# Sch_DSS2_NolanJennifer.net
KiCad netlist of a schematic drawn in Altium Designer
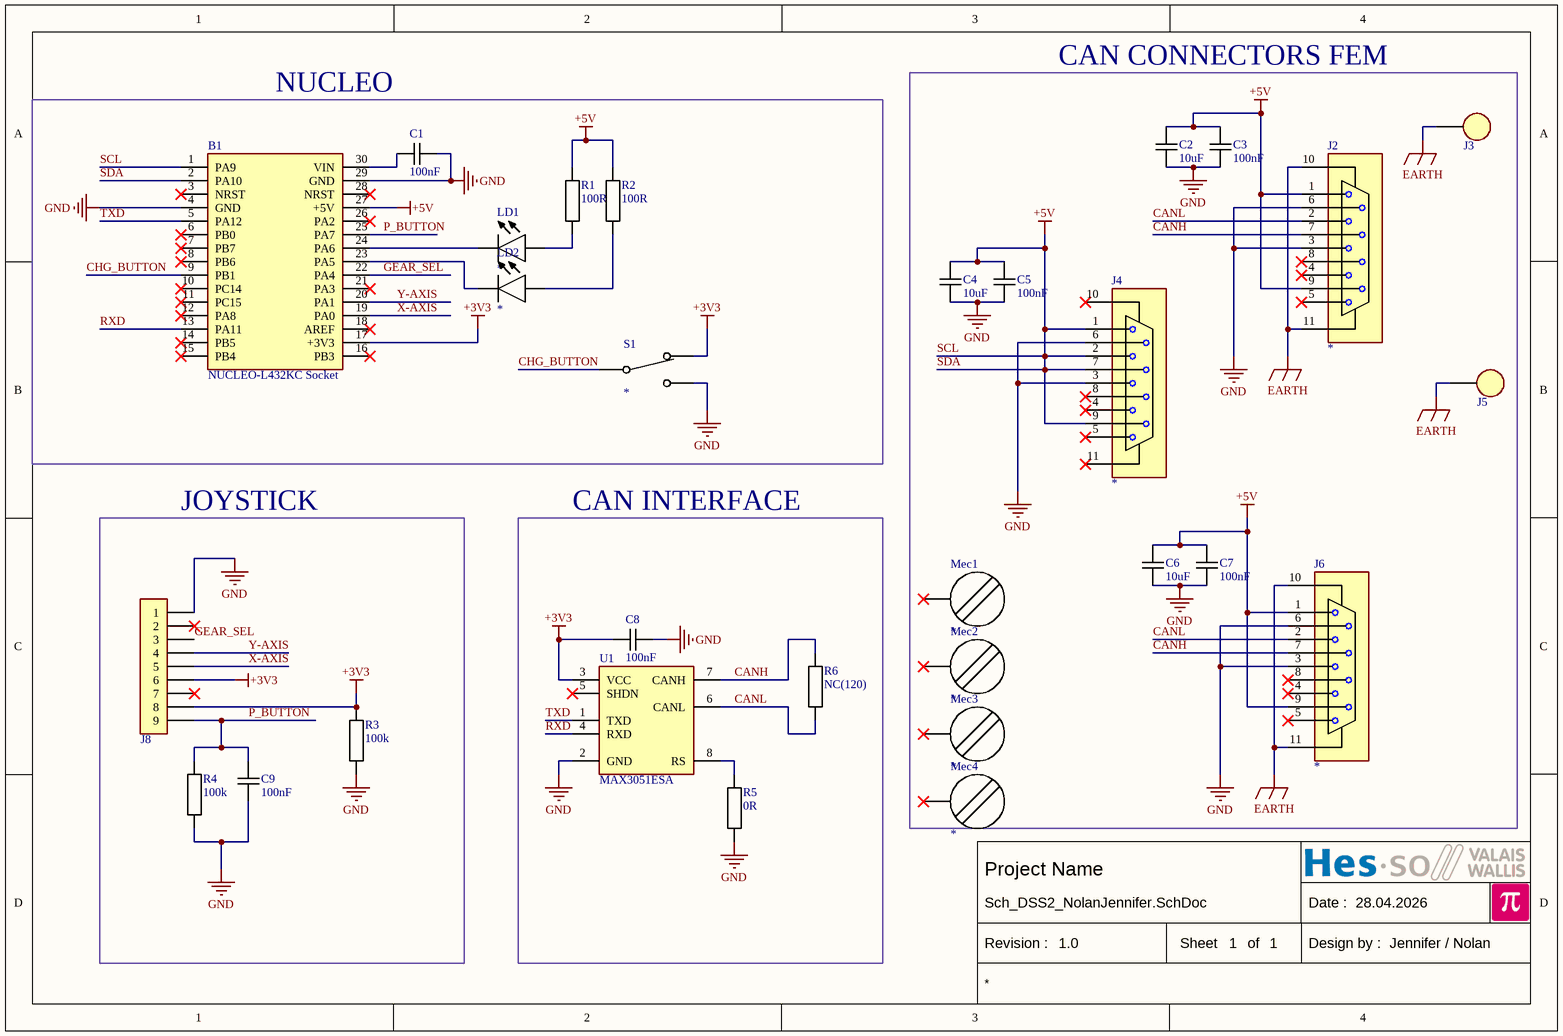
[diagram p0: Sch_DSS2_NolanJennifer.SchDoc]

(export (version "E")
  (design (tool "Eeschema 10.0.6"))
  (components
    (comp (ref "B1")
      (value "NUCLEO-L432KC Socket")
      (footprint "NUCLEO-L432KC Socket")
      (description "ARM Cortex based board")
      (libsource (lib "DevBoard") (part "NUCLEO-L432KC Socket"))
    )
    (comp (ref "C1")
      (value "100nF")
      (footprint "CAPACITOR 2012 REFLOW")
      (description "Capacitor")
      (libsource (lib "Capacitor") (part "Capacitor"))
    )
    (comp (ref "C2")
      (value "10uF")
      (footprint "CAPACITOR 2012 REFLOW")
      (description "Capacitor")
      (libsource (lib "Capacitor") (part "Capacitor"))
    )
    (comp (ref "C3")
      (value "100nF")
      (footprint "CAPACITOR 2012 REFLOW")
      (description "Capacitor")
      (libsource (lib "Capacitor") (part "Capacitor"))
    )
    (comp (ref "C4")
      (value "10uF")
      (footprint "CAPACITOR 2012 REFLOW")
      (description "Capacitor")
      (libsource (lib "Capacitor") (part "Capacitor"))
    )
    (comp (ref "C5")
      (value "100nF")
      (footprint "CAPACITOR 2012 REFLOW")
      (description "Capacitor")
      (libsource (lib "Capacitor") (part "Capacitor"))
    )
    (comp (ref "C6")
      (value "10uF")
      (footprint "CAPACITOR 2012 REFLOW")
      (description "Capacitor")
      (libsource (lib "Capacitor") (part "Capacitor"))
    )
    (comp (ref "C7")
      (value "100nF")
      (footprint "CAPACITOR 2012 REFLOW")
      (description "Capacitor")
      (libsource (lib "Capacitor") (part "Capacitor"))
    )
    (comp (ref "C8")
      (value "100nF")
      (footprint "CAPACITOR 2012 REFLOW")
      (description "Capacitor")
      (libsource (lib "Capacitor") (part "Capacitor"))
    )
    (comp (ref "C9")
      (value "100nF")
      (footprint "CAPACITOR 2012 REFLOW")
      (description "Capacitor")
      (libsource (lib "Capacitor") (part "Capacitor"))
    )
    (comp (ref "J2")
      (value "*")
      (footprint "D-SUB 9 FEM RND 205-00769")
      (description "D-Subminiature 9 way Socket Right Angle")
      (libsource (lib "Connector") (part "D-SUB 9 FEM GROUNDED"))
    )
    (comp (ref "J3")
      (value "3867B.68")
      (footprint "FASTON 6.3mm P5.0")
      (description "Faston Right angle Vogt 3867B.68")
      (libsource (lib "Connector") (part "FASTON 6.3mm P5.0"))
    )
    (comp (ref "J4")
      (value "*")
      (footprint "D-SUB 9 FEM RND 205-00769")
      (description "D-Subminiature 9 way Socket Right Angle")
      (libsource (lib "Connector") (part "D-SUB 9 FEM GROUNDED"))
    )
    (comp (ref "J5")
      (value "3867B.68")
      (footprint "FASTON 6.3mm P5.0")
      (description "Faston Right angle Vogt 3867B.68")
      (libsource (lib "Connector") (part "FASTON 6.3mm P5.0"))
    )
    (comp (ref "J6")
      (value "*")
      (footprint "D-SUB 9 FEM RND 205-00769")
      (description "D-Subminiature 9 way Socket Right Angle")
      (libsource (lib "Connector") (part "D-SUB 9 FEM GROUNDED"))
    )
    (comp (ref "J8")
      (value "*")
      (footprint "PinHeader1x9 P2.54")
      (description "Plug connector")
      (libsource (lib "PinHeader") (part "PinHeader1x9"))
    )
    (comp (ref "LD1")
      (value "*")
      (footprint "LED 3216 REFLOW")
      (description "LED generic")
      (libsource (lib "Diode") (part "LED"))
    )
    (comp (ref "LD2")
      (value "*")
      (footprint "LED 3216 REFLOW")
      (description "LED generic")
      (libsource (lib "Diode") (part "LED"))
    )
    (comp (ref "Mec1")
      (value "*")
      (footprint "Screw M3X5 Connected")
      (description "Screw Connected BN330")
      (libsource (lib "Mechanic") (part "Screw Connected"))
    )
    (comp (ref "Mec2")
      (value "*")
      (footprint "Screw M3X5 Connected")
      (description "Screw Connected BN330")
      (libsource (lib "Mechanic") (part "Screw Connected"))
    )
    (comp (ref "Mec3")
      (value "*")
      (footprint "Screw M3X5 Connected")
      (description "Screw Connected BN330")
      (libsource (lib "Mechanic") (part "Screw Connected"))
    )
    (comp (ref "Mec4")
      (value "*")
      (footprint "Screw M3X5 Connected")
      (description "Screw Connected BN330")
      (libsource (lib "Mechanic") (part "Screw Connected"))
    )
    (comp (ref "R1")
      (value "100R")
      (footprint "RESISTOR 2012 REFLOW")
      (description "Resistor")
      (libsource (lib "Resistor") (part "Resistor"))
    )
    (comp (ref "R2")
      (value "100R")
      (footprint "RESISTOR 2012 REFLOW")
      (description "Resistor")
      (libsource (lib "Resistor") (part "Resistor"))
    )
    (comp (ref "R3")
      (value "100k")
      (footprint "RESISTOR 2012 REFLOW")
      (description "Resistor")
      (libsource (lib "Resistor") (part "Resistor"))
    )
    (comp (ref "R4")
      (value "100k")
      (footprint "RESISTOR 2012 REFLOW")
      (description "Resistor")
      (libsource (lib "Resistor") (part "Resistor"))
    )
    (comp (ref "R5")
      (value "0R")
      (footprint "RESISTOR 2012 REFLOW")
      (description "Resistor")
      (libsource (lib "Resistor") (part "Resistor"))
    )
    (comp (ref "R6")
      (value "NC(120)")
      (footprint "RESISTOR 2012 REFLOW")
      (description "Resistor")
      (libsource (lib "Resistor") (part "Resistor"))
    )
    (comp (ref "S1")
      (value "*")
      (footprint "SLIDE SWITCH Knitter MFP120")
      (description "Slide Switch 1Pole ON-ON")
      (fields (field (name "ALTIUM_VALUE") "*"))
      (libsource (lib "Button") (part "Slide Switch 1Pole ON-ON"))
    )
    (comp (ref "U1")
      (value "MAX3051ESA")
      (footprint "SO8 P1.27 C4.0X5.0 H1.75")
      (description "+3.3V, 1Mbps, Low-Supply-Current CAN Transceiver")
      (libsource (lib "IntegratedCircuit") (part "MAX3051ESA"))
    )
  )
  (nets
    (net (code "1") (name "+3V3") (class "Default")
      (node (ref "B1") (pin "17") (pinfunction "+3V3_17") (pintype "passive"))
      (node (ref "C8") (pin "1") (pinfunction "1_1") (pintype "passive"))
      (node (ref "J8") (pin "6") (pinfunction "6_6") (pintype "passive"))
      (node (ref "J8") (pin "8") (pinfunction "8_8") (pintype "passive"))
      (node (ref "R3") (pin "2") (pinfunction "2_2") (pintype "passive"))
      (node (ref "S1") (pin "1") (pinfunction "NC_1") (pintype "passive"))
      (node (ref "U1") (pin "3") (pinfunction "VCC_3") (pintype "passive"))
    )
    (net (code "2") (name "+5V") (class "Default")
      (node (ref "B1") (pin "1") (pinfunction "PA9_1") (pintype "passive"))
      (node (ref "B1") (pin "2") (pinfunction "PA10_2") (pintype "passive"))
      (node (ref "B1") (pin "27") (pinfunction "+5V_27") (pintype "passive"))
      (node (ref "C2") (pin "2") (pinfunction "2_2") (pintype "passive"))
      (node (ref "C3") (pin "2") (pinfunction "2_2") (pintype "passive"))
      (node (ref "C4") (pin "2") (pinfunction "2_2") (pintype "passive"))
      (node (ref "C5") (pin "2") (pinfunction "2_2") (pintype "passive"))
      (node (ref "C6") (pin "2") (pinfunction "2_2") (pintype "passive"))
      (node (ref "C7") (pin "2") (pinfunction "2_2") (pintype "passive"))
      (node (ref "J2") (pin "1") (pintype "passive"))
      (node (ref "J2") (pin "9") (pintype "passive"))
      (node (ref "J4") (pin "1") (pintype "passive"))
      (node (ref "J4") (pin "2") (pintype "passive"))
      (node (ref "J4") (pin "7") (pintype "passive"))
      (node (ref "J4") (pin "9") (pintype "passive"))
      (node (ref "J6") (pin "1") (pintype "passive"))
      (node (ref "J6") (pin "9") (pintype "passive"))
      (node (ref "R1") (pin "2") (pinfunction "2_2") (pintype "passive"))
      (node (ref "R2") (pin "2") (pinfunction "2_2") (pintype "passive"))
    )
    (net (code "3") (name "/CANH") (class "Default")
      (node (ref "J2") (pin "7") (pintype "passive"))
      (node (ref "J6") (pin "7") (pintype "passive"))
      (node (ref "R6") (pin "2") (pinfunction "2_2") (pintype "passive"))
      (node (ref "U1") (pin "7") (pinfunction "CANH_7") (pintype "passive"))
    )
    (net (code "4") (name "/CANL") (class "Default")
      (node (ref "J2") (pin "2") (pintype "passive"))
      (node (ref "J6") (pin "2") (pintype "passive"))
      (node (ref "R6") (pin "1") (pinfunction "1_1") (pintype "passive"))
      (node (ref "U1") (pin "6") (pinfunction "CANL_6") (pintype "passive"))
    )
    (net (code "5") (name "/CHG_BUTTON") (class "Default")
      (node (ref "B1") (pin "9") (pinfunction "PB1_9") (pintype "passive"))
      (node (ref "S1") (pin "2") (pinfunction "com_2") (pintype "passive"))
    )
    (net (code "6") (name "/GEAR_SEL") (class "Default")
      (node (ref "B1") (pin "22") (pinfunction "PA4_22") (pintype "passive"))
      (node (ref "J8") (pin "3") (pinfunction "3_3") (pintype "passive"))
    )
    (net (code "7") (name "/P_BUTTON") (class "Default")
      (node (ref "B1") (pin "25") (pinfunction "PA7_25") (pintype "passive"))
      (node (ref "C9") (pin "2") (pinfunction "2_2") (pintype "passive"))
      (node (ref "J8") (pin "9") (pinfunction "9_9") (pintype "passive"))
      (node (ref "R4") (pin "2") (pinfunction "2_2") (pintype "passive"))
    )
    (net (code "8") (name "/RXD") (class "Default")
      (node (ref "B1") (pin "13") (pinfunction "PA11_13") (pintype "passive"))
      (node (ref "U1") (pin "4") (pinfunction "RXD_4") (pintype "passive"))
    )
    (net (code "9") (name "/TXD") (class "Default")
      (node (ref "B1") (pin "5") (pinfunction "PA12_5") (pintype "passive"))
      (node (ref "U1") (pin "1") (pinfunction "TXD_1") (pintype "passive"))
    )
    (net (code "10") (name "/X-AXIS") (class "Default")
      (node (ref "B1") (pin "19") (pinfunction "PA0_19") (pintype "passive"))
      (node (ref "J8") (pin "5") (pinfunction "5_5") (pintype "passive"))
    )
    (net (code "11") (name "/Y-AXIS") (class "Default")
      (node (ref "B1") (pin "20") (pinfunction "PA1_20") (pintype "passive"))
      (node (ref "J8") (pin "4") (pinfunction "4_4") (pintype "passive"))
    )
    (net (code "12") (name "EARTH") (class "Default")
      (node (ref "J2") (pin "10") (pintype "passive"))
      (node (ref "J2") (pin "11") (pintype "passive"))
      (node (ref "J3") (pin "1") (pinfunction "1_1") (pintype "passive"))
      (node (ref "J5") (pin "1") (pinfunction "1_1") (pintype "passive"))
      (node (ref "J6") (pin "10") (pintype "passive"))
      (node (ref "J6") (pin "11") (pintype "passive"))
    )
    (net (code "13") (name "GND") (class "Default")
      (node (ref "B1") (pin "29") (pinfunction "GND_29") (pintype "passive"))
      (node (ref "B1") (pin "4") (pinfunction "GND_4") (pintype "passive"))
      (node (ref "C1") (pin "2") (pinfunction "2_2") (pintype "passive"))
      (node (ref "C2") (pin "1") (pinfunction "1_1") (pintype "passive"))
      (node (ref "C3") (pin "1") (pinfunction "1_1") (pintype "passive"))
      (node (ref "C4") (pin "1") (pinfunction "1_1") (pintype "passive"))
      (node (ref "C5") (pin "1") (pinfunction "1_1") (pintype "passive"))
      (node (ref "C6") (pin "1") (pinfunction "1_1") (pintype "passive"))
      (node (ref "C7") (pin "1") (pinfunction "1_1") (pintype "passive"))
      (node (ref "C8") (pin "2") (pinfunction "2_2") (pintype "passive"))
      (node (ref "C9") (pin "1") (pinfunction "1_1") (pintype "passive"))
      (node (ref "J2") (pin "3") (pintype "passive"))
      (node (ref "J2") (pin "6") (pintype "passive"))
      (node (ref "J4") (pin "3") (pintype "passive"))
      (node (ref "J4") (pin "6") (pintype "passive"))
      (node (ref "J6") (pin "3") (pintype "passive"))
      (node (ref "J6") (pin "6") (pintype "passive"))
      (node (ref "J8") (pin "1") (pinfunction "1_1") (pintype "passive"))
      (node (ref "R3") (pin "1") (pinfunction "1_1") (pintype "passive"))
      (node (ref "R4") (pin "1") (pinfunction "1_1") (pintype "passive"))
      (node (ref "R5") (pin "1") (pinfunction "1_1") (pintype "passive"))
      (node (ref "S1") (pin "3") (pinfunction "NO_3") (pintype "passive"))
      (node (ref "U1") (pin "2") (pinfunction "GND_2") (pintype "passive"))
    )
    (net (code "14") (name "Net-(B1-PA5)") (class "Default")
      (node (ref "B1") (pin "23") (pinfunction "PA5_23") (pintype "passive"))
      (node (ref "LD2") (pin "1") (pinfunction "C_1") (pintype "passive"))
    )
    (net (code "15") (name "Net-(B1-PA6)") (class "Default")
      (node (ref "B1") (pin "24") (pinfunction "PA6_24") (pintype "passive"))
      (node (ref "LD1") (pin "1") (pinfunction "C_1") (pintype "passive"))
    )
    (net (code "16") (name "Net-(B1-VIN)") (class "Default")
      (node (ref "B1") (pin "30") (pinfunction "VIN_30") (pintype "passive"))
      (node (ref "C1") (pin "1") (pinfunction "1_1") (pintype "passive"))
    )
    (net (code "17") (name "Net-(LD1-A)") (class "Default")
      (node (ref "LD1") (pin "2") (pinfunction "A_2") (pintype "passive"))
      (node (ref "R1") (pin "1") (pinfunction "1_1") (pintype "passive"))
    )
    (net (code "18") (name "Net-(LD2-A)") (class "Default")
      (node (ref "LD2") (pin "2") (pinfunction "A_2") (pintype "passive"))
      (node (ref "R2") (pin "1") (pinfunction "1_1") (pintype "passive"))
    )
    (net (code "19") (name "Net-(U1-RS)") (class "Default")
      (node (ref "R5") (pin "2") (pinfunction "2_2") (pintype "passive"))
      (node (ref "U1") (pin "8") (pinfunction "RS_8") (pintype "passive"))
    )
    (net (code "20") (name "unconnected-(B1-AREF-Pad18)") (class "Default")
      (node (ref "B1") (pin "18") (pinfunction "AREF_18") (pintype "passive+no_connect"))
    )
    (net (code "21") (name "unconnected-(B1-NRST-Pad3)") (class "Default")
      (node (ref "B1") (pin "3") (pinfunction "NRST_3") (pintype "passive+no_connect"))
    )
    (net (code "22") (name "unconnected-(B1-NRST-Pad28)") (class "Default")
      (node (ref "B1") (pin "28") (pinfunction "NRST_28") (pintype "passive+no_connect"))
    )
    (net (code "23") (name "unconnected-(B1-PA2-Pad26)") (class "Default")
      (node (ref "B1") (pin "26") (pinfunction "PA2_26") (pintype "passive+no_connect"))
    )
    (net (code "24") (name "unconnected-(B1-PA3-Pad21)") (class "Default")
      (node (ref "B1") (pin "21") (pinfunction "PA3_21") (pintype "passive+no_connect"))
    )
    (net (code "25") (name "unconnected-(B1-PA8-Pad12)") (class "Default")
      (node (ref "B1") (pin "12") (pinfunction "PA8_12") (pintype "passive+no_connect"))
    )
    (net (code "26") (name "unconnected-(B1-PB0-Pad6)") (class "Default")
      (node (ref "B1") (pin "6") (pinfunction "PB0_6") (pintype "passive+no_connect"))
    )
    (net (code "27") (name "unconnected-(B1-PB3-Pad16)") (class "Default")
      (node (ref "B1") (pin "16") (pinfunction "PB3_16") (pintype "passive+no_connect"))
    )
    (net (code "28") (name "unconnected-(B1-PB4-Pad15)") (class "Default")
      (node (ref "B1") (pin "15") (pinfunction "PB4_15") (pintype "passive+no_connect"))
    )
    (net (code "29") (name "unconnected-(B1-PB5-Pad14)") (class "Default")
      (node (ref "B1") (pin "14") (pinfunction "PB5_14") (pintype "passive+no_connect"))
    )
    (net (code "30") (name "unconnected-(B1-PB6-Pad8)") (class "Default")
      (node (ref "B1") (pin "8") (pinfunction "PB6_8") (pintype "passive+no_connect"))
    )
    (net (code "31") (name "unconnected-(B1-PB7-Pad7)") (class "Default")
      (node (ref "B1") (pin "7") (pinfunction "PB7_7") (pintype "passive+no_connect"))
    )
    (net (code "32") (name "unconnected-(B1-PC14-Pad10)") (class "Default")
      (node (ref "B1") (pin "10") (pinfunction "PC14_10") (pintype "passive+no_connect"))
    )
    (net (code "33") (name "unconnected-(B1-PC15-Pad11)") (class "Default")
      (node (ref "B1") (pin "11") (pinfunction "PC15_11") (pintype "passive+no_connect"))
    )
    (net (code "34") (name "unconnected-(J2-Pad4)") (class "Default")
      (node (ref "J2") (pin "4") (pintype "passive+no_connect"))
    )
    (net (code "35") (name "unconnected-(J2-Pad5)") (class "Default")
      (node (ref "J2") (pin "5") (pintype "passive+no_connect"))
    )
    (net (code "36") (name "unconnected-(J2-Pad8)") (class "Default")
      (node (ref "J2") (pin "8") (pintype "passive+no_connect"))
    )
    (net (code "37") (name "unconnected-(J4-Pad4)") (class "Default")
      (node (ref "J4") (pin "4") (pintype "passive+no_connect"))
    )
    (net (code "38") (name "unconnected-(J4-Pad5)") (class "Default")
      (node (ref "J4") (pin "5") (pintype "passive+no_connect"))
    )
    (net (code "39") (name "unconnected-(J4-Pad8)") (class "Default")
      (node (ref "J4") (pin "8") (pintype "passive+no_connect"))
    )
    (net (code "40") (name "unconnected-(J4-Pad10)") (class "Default")
      (node (ref "J4") (pin "10") (pintype "passive+no_connect"))
    )
    (net (code "41") (name "unconnected-(J4-Pad11)") (class "Default")
      (node (ref "J4") (pin "11") (pintype "passive+no_connect"))
    )
    (net (code "42") (name "unconnected-(J6-Pad4)") (class "Default")
      (node (ref "J6") (pin "4") (pintype "passive+no_connect"))
    )
    (net (code "43") (name "unconnected-(J6-Pad5)") (class "Default")
      (node (ref "J6") (pin "5") (pintype "passive+no_connect"))
    )
    (net (code "44") (name "unconnected-(J6-Pad8)") (class "Default")
      (node (ref "J6") (pin "8") (pintype "passive+no_connect"))
    )
    (net (code "45") (name "unconnected-(J8-Pad2)") (class "Default")
      (node (ref "J8") (pin "2") (pinfunction "2_2") (pintype "passive+no_connect"))
    )
    (net (code "46") (name "unconnected-(J8-Pad7)") (class "Default")
      (node (ref "J8") (pin "7") (pinfunction "7_7") (pintype "passive+no_connect"))
    )
    (net (code "47") (name "unconnected-(Mec1-Pad1)") (class "Default")
      (node (ref "Mec1") (pin "1") (pinfunction "1_1") (pintype "passive+no_connect"))
    )
    (net (code "48") (name "unconnected-(Mec2-Pad1)") (class "Default")
      (node (ref "Mec2") (pin "1") (pinfunction "1_1") (pintype "passive+no_connect"))
    )
    (net (code "49") (name "unconnected-(Mec3-Pad1)") (class "Default")
      (node (ref "Mec3") (pin "1") (pinfunction "1_1") (pintype "passive+no_connect"))
    )
    (net (code "50") (name "unconnected-(Mec4-Pad1)") (class "Default")
      (node (ref "Mec4") (pin "1") (pinfunction "1_1") (pintype "passive+no_connect"))
    )
    (net (code "51") (name "unconnected-(U1-SHDN-Pad5)") (class "Default")
      (node (ref "U1") (pin "5") (pinfunction "SHDN_5") (pintype "passive+no_connect"))
    )
  )
)
